# 07-DPLL-1.net
KiCad netlist of a schematic drawn in Altium Designer
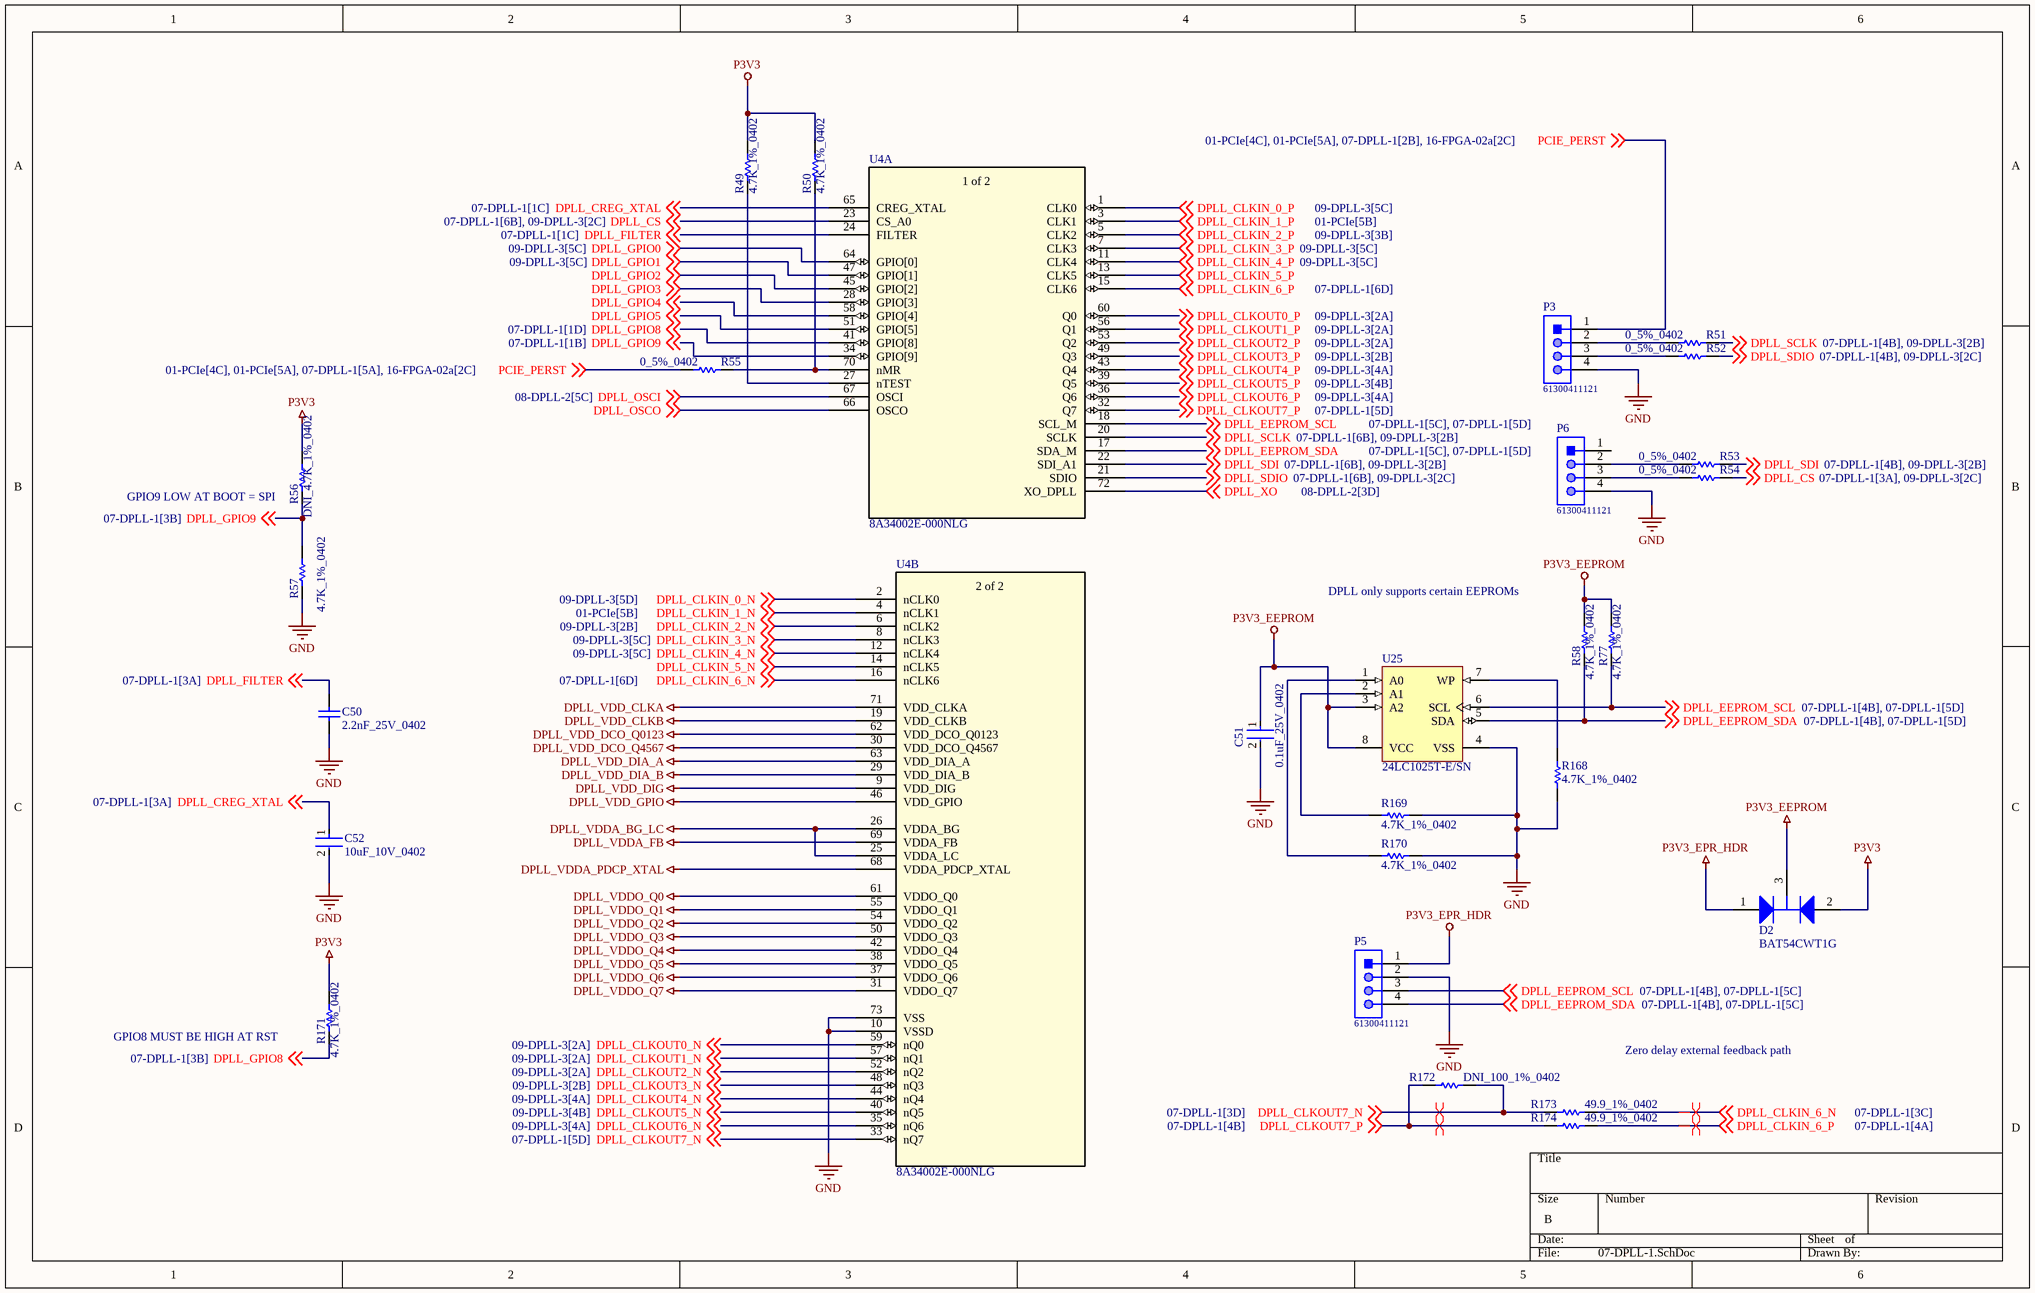
[diagram p0: 07-DPLL-1.SchDoc]

(export (version "E")
  (design (tool "Eeschema 10.0.6"))
  (components
    (comp (ref "C50")
      (value "2.2nF_25V_0402")
      (footprint "CAPC1005X56X25LL10T15")
      (fields
        (field (name "MANUFACTURER") "AVX Interconnect / Elco")
        (field (name "PART NUMBER") "04025C222JAT2A")
      )
      (libsource (lib "Altium Content Vault") (part "CAP"))
    )
    (comp (ref "C51")
      (value "0.1uF_25V_0402")
      (footprint "FP-0402-L_1_0_1-W_0_5_0_1-IPC_C")
      (description "General Purpose Ceramic Capacitor, 0402, 100nF, 10%, X7R, 15%, 25V")
      (fields (field (name "VOLTAGE") "25V") (field (name "TOLERANCE") "10%"))
      (libsource (lib "Altium Content Vault") (part "b4654b650e69147ec39a6b967a45e02"))
    )
    (comp (ref "C52")
      (value "10uF_10V_0402")
      (footprint "FP-CL05A106MP5NUNC-MFG")
      (description "CAP CER 10UF 10V X5R 0402")
      (fields
        (field (name "OCTOPART") "https://octopart.com/cl05a106mp5nunc-samsung-22457395")
        (field (name "TOLERANCE") "20%")
      )
      (libsource (lib "Altium Content Vault") (part "b4654b650e69147ec39a6b967a45e02"))
    )
    (comp (ref "D2")
      (value "BAT54CWT1G")
      (footprint "ONSC-SOT-323-3-419-04_V")
      (description "Dual Series Cathode Schottky Barrier Diodes, 3-Pin SOT-323, Pb-Free, Tape and Reel")
      (fields (field (name "MANUFACTURER") "On Semiconductor"))
      (libsource (lib "Altium Content Vault") (part "ONSC-D-A1A2K3-3"))
    )
    (comp (ref "P3")
      (value "61300411121")
      (footprint "61300411121")
      (description "THT Vertical Pin Header WR-PHD, Pitch 2.54 mm, Single Row, 4 pins")
      (fields (field (name "MANUFACTURER") "Wurth Elektronik") (field (name "PUBLISHER") "WurthElektronik"))
      (libsource (lib "Altium Content Vault") (part "WE-CN-1P-M-R4"))
    )
    (comp (ref "P5")
      (value "61300411121")
      (footprint "61300411121")
      (description "THT Vertical Pin Header WR-PHD, Pitch 2.54 mm, Single Row, 4 pins")
      (fields (field (name "MANUFACTURER") "Wurth Elektronik") (field (name "PUBLISHER") "WurthElektronik"))
      (libsource (lib "Altium Content Vault") (part "WE-CN-1P-M-R4"))
    )
    (comp (ref "P6")
      (value "61300411121")
      (footprint "61300411121")
      (description "THT Vertical Pin Header WR-PHD, Pitch 2.54 mm, Single Row, 4 pins")
      (fields (field (name "MANUFACTURER") "Wurth Elektronik") (field (name "PUBLISHER") "WurthElektronik"))
      (libsource (lib "Altium Content Vault") (part "WE-CN-1P-M-R4"))
    )
    (comp (ref "R49")
      (value "4.7K_1%_0402")
      (footprint "RESC1005X40X25NL10T10")
      (fields (field (name "MANUFACTURER") "Bourns") (field (name "PART NUMBER") "CR0402-FX-4701GLF"))
      (libsource (lib "Altium Content Vault") (part "RES"))
    )
    (comp (ref "R50")
      (value "4.7K_1%_0402")
      (footprint "RESC1005X40X25NL10T10")
      (fields (field (name "MANUFACTURER") "Bourns") (field (name "PART NUMBER") "CR0402-FX-4701GLF"))
      (libsource (lib "Altium Content Vault") (part "RES"))
    )
    (comp (ref "R51")
      (value "0_5%_0402")
      (footprint "RESC1005X40X25LL10T10")
      (fields (field (name "MANUFACTURER") "KOA Speer") (field (name "PART NUMBER") "RK73Z1ETTP"))
      (libsource (lib "Altium Content Vault") (part "RES"))
    )
    (comp (ref "R52")
      (value "0_5%_0402")
      (footprint "RESC1005X40X25LL10T10")
      (fields (field (name "MANUFACTURER") "KOA Speer") (field (name "PART NUMBER") "RK73Z1ETTP"))
      (libsource (lib "Altium Content Vault") (part "RES"))
    )
    (comp (ref "R53")
      (value "0_5%_0402")
      (footprint "RESC1005X40X25LL10T10")
      (fields (field (name "MANUFACTURER") "KOA Speer") (field (name "PART NUMBER") "RK73Z1ETTP"))
      (libsource (lib "Altium Content Vault") (part "RES"))
    )
    (comp (ref "R54")
      (value "0_5%_0402")
      (footprint "RESC1005X40X25LL10T10")
      (fields (field (name "MANUFACTURER") "KOA Speer") (field (name "PART NUMBER") "RK73Z1ETTP"))
      (libsource (lib "Altium Content Vault") (part "RES"))
    )
    (comp (ref "R55")
      (value "0_5%_0402")
      (footprint "RESC1005X40X25LL10T10")
      (fields (field (name "MANUFACTURER") "KOA Speer") (field (name "PART NUMBER") "RK73Z1ETTP"))
      (libsource (lib "Altium Content Vault") (part "RES"))
    )
    (comp (ref "R56")
      (value "DNI_4.7K_1%_0402")
      (footprint "RESC1005X40X25NL10T10")
      (fields (field (name "MANUFACTURER") "Bourns") (field (name "PART NUMBER") "CR0402-FX-4701GLF"))
      (libsource (lib "Altium Content Vault") (part "RES"))
    )
    (comp (ref "R57")
      (value "4.7K_1%_0402")
      (footprint "RESC1005X40X25NL10T10")
      (fields (field (name "MANUFACTURER") "Bourns") (field (name "PART NUMBER") "CR0402-FX-4701GLF"))
      (libsource (lib "Altium Content Vault") (part "RES"))
    )
    (comp (ref "R58")
      (value "4.7K_1%_0402")
      (footprint "RESC1005X40X25NL10T10")
      (fields (field (name "MANUFACTURER") "Bourns") (field (name "PART NUMBER") "CR0402-FX-4701GLF"))
      (libsource (lib "Altium Content Vault") (part "RES"))
    )
    (comp (ref "R77")
      (value "4.7K_1%_0402")
      (footprint "RESC1005X40X25NL10T10")
      (fields (field (name "MANUFACTURER") "Bourns") (field (name "PART NUMBER") "CR0402-FX-4701GLF"))
      (libsource (lib "Altium Content Vault") (part "RES"))
    )
    (comp (ref "R168")
      (value "4.7K_1%_0402")
      (footprint "RESC1005X40X25NL10T10")
      (fields (field (name "MANUFACTURER") "Bourns") (field (name "PART NUMBER") "CR0402-FX-4701GLF"))
      (libsource (lib "Altium Content Vault") (part "RES"))
    )
    (comp (ref "R169")
      (value "4.7K_1%_0402")
      (footprint "RESC1005X40X25NL10T10")
      (fields (field (name "MANUFACTURER") "Bourns") (field (name "PART NUMBER") "CR0402-FX-4701GLF"))
      (libsource (lib "Altium Content Vault") (part "RES"))
    )
    (comp (ref "R170")
      (value "4.7K_1%_0402")
      (footprint "RESC1005X40X25NL10T10")
      (fields (field (name "MANUFACTURER") "Bourns") (field (name "PART NUMBER") "CR0402-FX-4701GLF"))
      (libsource (lib "Altium Content Vault") (part "RES"))
    )
    (comp (ref "R171")
      (value "4.7K_1%_0402")
      (footprint "RESC1005X40X25NL10T10")
      (fields (field (name "MANUFACTURER") "Bourns") (field (name "PART NUMBER") "CR0402-FX-4701GLF"))
      (libsource (lib "Altium Content Vault") (part "RES"))
    )
    (comp (ref "R172")
      (value "DNI_100_1%_0402")
      (footprint "RESC1005X40X25LL05T05")
      (description "Chip Resistor, 100 Ohm, +/- 1%, 100 mW, -55 to 155 degC, 0402 (1005 Metric), RoHS, Tape and Reel")
      (fields (field (name "MANUFACTURER") "Basic Passives") (field (name "TOLERANCE") "1%"))
      (libsource (lib "Altium Content Vault") (part "RES-2"))
    )
    (comp (ref "R173")
      (value "49.9_1%_0402")
      (footprint "RESC1005X40X25NL10T10")
      (fields (field (name "PART NUMBER") "RK73H1ETTP49R9F") (field (name "MANUFACTURER") "KOA Speer"))
      (libsource (lib "Altium Content Vault") (part "RES"))
    )
    (comp (ref "R174")
      (value "49.9_1%_0402")
      (footprint "RESC1005X40X25NL10T10")
      (fields (field (name "PART NUMBER") "RK73H1ETTP49R9F") (field (name "MANUFACTURER") "KOA Speer"))
      (libsource (lib "Altium Content Vault") (part "RES"))
    )
    (comp (ref "U4")
      (value "8A34002E-000NLG")
      (footprint "QFN_2E-000NLG_REN")
      (description "No Description Available")
      (libsource (lib "8A34002E-000NLG") (part "8A34002E-000NLG"))
    )
    (comp (ref "U25")
      (value "24LC1025T-E/SN")
      (footprint "SOIC-SN8_M")
      (description "1 Mbit, 400kHz, 2.5V, 8-Pin SOIC 150mil, Extended Temperature, Tape and Reel")
      (libsource (lib "Altium Content Vault") (part "MEM-SEEPROM-34AA02-IL8"))
    )
  )
  (nets
    (net (code "1") (name "DPLL_CLKIN_0_N") (class "Default")
      (node (ref "U4") (pin "2") (pinfunction "nCLK0_2") (pintype "passive"))
    )
    (net (code "2") (name "DPLL_CLKIN_0_P") (class "Default")
      (node (ref "U4") (pin "1") (pinfunction "CLK0_1") (pintype "bidirectional"))
    )
    (net (code "3") (name "DPLL_CLKIN_1_N") (class "Default")
      (node (ref "U4") (pin "4") (pinfunction "nCLK1_4") (pintype "passive"))
    )
    (net (code "4") (name "DPLL_CLKIN_1_P") (class "Default")
      (node (ref "U4") (pin "3") (pinfunction "CLK1_3") (pintype "bidirectional"))
    )
    (net (code "5") (name "DPLL_CLKIN_2_N") (class "Default")
      (node (ref "U4") (pin "6") (pinfunction "nCLK2_6") (pintype "passive"))
    )
    (net (code "6") (name "DPLL_CLKIN_2_P") (class "Default")
      (node (ref "U4") (pin "5") (pinfunction "CLK2_5") (pintype "bidirectional"))
    )
    (net (code "7") (name "DPLL_CLKIN_3_N") (class "Default")
      (node (ref "U4") (pin "8") (pinfunction "nCLK3_8") (pintype "passive"))
    )
    (net (code "8") (name "DPLL_CLKIN_3_P") (class "Default")
      (node (ref "U4") (pin "7") (pinfunction "CLK3_7") (pintype "bidirectional"))
    )
    (net (code "9") (name "DPLL_CLKIN_4_N") (class "Default")
      (node (ref "U4") (pin "12") (pinfunction "nCLK4_12") (pintype "passive"))
    )
    (net (code "10") (name "DPLL_CLKIN_4_P") (class "Default")
      (node (ref "U4") (pin "11") (pinfunction "CLK4_11") (pintype "bidirectional"))
    )
    (net (code "11") (name "DPLL_CLKIN_5_N") (class "Default")
      (node (ref "U4") (pin "14") (pinfunction "nCLK5_14") (pintype "passive"))
    )
    (net (code "12") (name "DPLL_CLKIN_5_P") (class "Default")
      (node (ref "U4") (pin "13") (pinfunction "CLK5_13") (pintype "bidirectional"))
    )
    (net (code "13") (name "DPLL_CLKIN_6_N") (class "Default")
      (node (ref "R173") (pin "2") (pinfunction "2_2") (pintype "passive"))
      (node (ref "U4") (pin "16") (pinfunction "nCLK6_16") (pintype "passive"))
    )
    (net (code "14") (name "DPLL_CLKIN_6_P") (class "Default")
      (node (ref "R174") (pin "2") (pinfunction "2_2") (pintype "passive"))
      (node (ref "U4") (pin "15") (pinfunction "CLK6_15") (pintype "bidirectional"))
    )
    (net (code "15") (name "DPLL_CLKOUT0_N") (class "Default")
      (node (ref "U4") (pin "59") (pinfunction "nQ0_59") (pintype "bidirectional"))
    )
    (net (code "16") (name "DPLL_CLKOUT0_P") (class "Default")
      (node (ref "U4") (pin "60") (pinfunction "Q0_60") (pintype "bidirectional"))
    )
    (net (code "17") (name "DPLL_CLKOUT1_N") (class "Default")
      (node (ref "U4") (pin "57") (pinfunction "nQ1_57") (pintype "bidirectional"))
    )
    (net (code "18") (name "DPLL_CLKOUT1_P") (class "Default")
      (node (ref "U4") (pin "56") (pinfunction "Q1_56") (pintype "bidirectional"))
    )
    (net (code "19") (name "DPLL_CLKOUT2_N") (class "Default")
      (node (ref "U4") (pin "52") (pinfunction "nQ2_52") (pintype "bidirectional"))
    )
    (net (code "20") (name "DPLL_CLKOUT2_P") (class "Default")
      (node (ref "U4") (pin "53") (pinfunction "Q2_53") (pintype "bidirectional"))
    )
    (net (code "21") (name "DPLL_CLKOUT3_N") (class "Default")
      (node (ref "U4") (pin "48") (pinfunction "nQ3_48") (pintype "bidirectional"))
    )
    (net (code "22") (name "DPLL_CLKOUT3_P") (class "Default")
      (node (ref "U4") (pin "49") (pinfunction "Q3_49") (pintype "bidirectional"))
    )
    (net (code "23") (name "DPLL_CLKOUT4_N") (class "Default")
      (node (ref "U4") (pin "44") (pinfunction "nQ4_44") (pintype "bidirectional"))
    )
    (net (code "24") (name "DPLL_CLKOUT4_P") (class "Default")
      (node (ref "U4") (pin "43") (pinfunction "Q4_43") (pintype "bidirectional"))
    )
    (net (code "25") (name "DPLL_CLKOUT5_N") (class "Default")
      (node (ref "U4") (pin "40") (pinfunction "nQ5_40") (pintype "bidirectional"))
    )
    (net (code "26") (name "DPLL_CLKOUT5_P") (class "Default")
      (node (ref "U4") (pin "39") (pinfunction "Q5_39") (pintype "bidirectional"))
    )
    (net (code "27") (name "DPLL_CLKOUT6_N") (class "Default")
      (node (ref "U4") (pin "35") (pinfunction "nQ6_35") (pintype "bidirectional"))
    )
    (net (code "28") (name "DPLL_CLKOUT6_P") (class "Default")
      (node (ref "U4") (pin "36") (pinfunction "Q6_36") (pintype "bidirectional"))
    )
    (net (code "29") (name "DPLL_CLKOUT7_N") (class "Default")
      (node (ref "R172") (pin "2") (pinfunction "2_2") (pintype "passive"))
      (node (ref "R173") (pin "1") (pinfunction "1_1") (pintype "passive"))
      (node (ref "U4") (pin "33") (pinfunction "nQ7_33") (pintype "bidirectional"))
    )
    (net (code "30") (name "DPLL_CLKOUT7_P") (class "Default")
      (node (ref "R172") (pin "1") (pinfunction "1_1") (pintype "passive"))
      (node (ref "R174") (pin "1") (pinfunction "1_1") (pintype "passive"))
      (node (ref "U4") (pin "32") (pinfunction "Q7_32") (pintype "bidirectional"))
    )
    (net (code "31") (name "DPLL_CREG_XTAL") (class "Default")
      (node (ref "C52") (pin "1") (pinfunction "1_1") (pintype "passive"))
      (node (ref "U4") (pin "65") (pinfunction "CREG_XTAL_65") (pintype "passive"))
    )
    (net (code "32") (name "DPLL_CS") (class "Default")
      (node (ref "R54") (pin "2") (pinfunction "2_2") (pintype "passive"))
      (node (ref "U4") (pin "23") (pinfunction "CS_A0_23") (pintype "passive"))
    )
    (net (code "33") (name "DPLL_EEPROM_SCL") (class "Default")
      (node (ref "P5") (pin "3") (pinfunction "3_3") (pintype "passive"))
      (node (ref "R77") (pin "2") (pinfunction "2_2") (pintype "passive"))
      (node (ref "U25") (pin "6") (pinfunction "SCL_6") (pintype "input"))
      (node (ref "U4") (pin "18") (pinfunction "SCL_M_18") (pintype "passive"))
    )
    (net (code "34") (name "DPLL_EEPROM_SDA") (class "Default")
      (node (ref "P5") (pin "4") (pinfunction "4_4") (pintype "passive"))
      (node (ref "R58") (pin "2") (pinfunction "2_2") (pintype "passive"))
      (node (ref "U25") (pin "5") (pinfunction "SDA_5") (pintype "bidirectional"))
      (node (ref "U4") (pin "17") (pinfunction "SDA_M_17") (pintype "passive"))
    )
    (net (code "35") (name "DPLL_FILTER") (class "Default")
      (node (ref "C50") (pin "2") (pinfunction "2_2") (pintype "passive"))
      (node (ref "U4") (pin "24") (pinfunction "FILTER_24") (pintype "passive"))
    )
    (net (code "36") (name "DPLL_GPIO0") (class "Default")
      (node (ref "U4") (pin "64") (pinfunction "GPIO[0]_64") (pintype "bidirectional"))
    )
    (net (code "37") (name "DPLL_GPIO1") (class "Default")
      (node (ref "U4") (pin "47") (pinfunction "GPIO[1]_47") (pintype "bidirectional"))
    )
    (net (code "38") (name "DPLL_GPIO2") (class "Default")
      (node (ref "U4") (pin "45") (pinfunction "GPIO[2]_45") (pintype "bidirectional"))
    )
    (net (code "39") (name "DPLL_GPIO3") (class "Default")
      (node (ref "U4") (pin "28") (pinfunction "GPIO[3]_28") (pintype "bidirectional"))
    )
    (net (code "40") (name "DPLL_GPIO4") (class "Default")
      (node (ref "U4") (pin "58") (pinfunction "GPIO[4]_58") (pintype "bidirectional"))
    )
    (net (code "41") (name "DPLL_GPIO5") (class "Default")
      (node (ref "U4") (pin "51") (pinfunction "GPIO[5]_51") (pintype "bidirectional"))
    )
    (net (code "42") (name "DPLL_GPIO8") (class "Default")
      (node (ref "R171") (pin "2") (pinfunction "2_2") (pintype "passive"))
      (node (ref "U4") (pin "41") (pinfunction "GPIO[8]_41") (pintype "bidirectional"))
    )
    (net (code "43") (name "DPLL_GPIO9") (class "Default")
      (node (ref "R56") (pin "2") (pinfunction "2_2") (pintype "passive"))
      (node (ref "R57") (pin "2") (pinfunction "2_2") (pintype "passive"))
      (node (ref "U4") (pin "34") (pinfunction "GPIO[9]_34") (pintype "bidirectional"))
    )
    (net (code "44") (name "DPLL_OSCI") (class "Default")
      (node (ref "U4") (pin "67") (pinfunction "OSCI_67") (pintype "passive"))
    )
    (net (code "45") (name "DPLL_OSCO") (class "Default")
      (node (ref "U4") (pin "66") (pinfunction "OSCO_66") (pintype "passive"))
    )
    (net (code "46") (name "DPLL_SCLK") (class "Default")
      (node (ref "R51") (pin "2") (pinfunction "2_2") (pintype "passive"))
      (node (ref "U4") (pin "20") (pinfunction "SCLK_20") (pintype "passive"))
    )
    (net (code "47") (name "DPLL_SDI") (class "Default")
      (node (ref "R53") (pin "2") (pinfunction "2_2") (pintype "passive"))
      (node (ref "U4") (pin "22") (pinfunction "SDI_A1_22") (pintype "passive"))
    )
    (net (code "48") (name "DPLL_SDIO") (class "Default")
      (node (ref "R52") (pin "2") (pinfunction "2_2") (pintype "passive"))
      (node (ref "U4") (pin "21") (pinfunction "SDIO_21") (pintype "passive"))
    )
    (net (code "49") (name "DPLL_VDDA_BG_LC") (class "Default")
      (node (ref "U4") (pin "25") (pinfunction "VDDA_LC_25") (pintype "power_in"))
      (node (ref "U4") (pin "26") (pinfunction "VDDA_BG_26") (pintype "power_in"))
    )
    (net (code "50") (name "DPLL_VDDA_FB") (class "Default")
      (node (ref "U4") (pin "69") (pinfunction "VDDA_FB_69") (pintype "power_in"))
    )
    (net (code "51") (name "DPLL_VDDA_PDCP_XTAL") (class "Default")
      (node (ref "U4") (pin "68") (pinfunction "VDDA_PDCP_XTAL_68") (pintype "power_in"))
    )
    (net (code "52") (name "DPLL_VDDO_Q0") (class "Default")
      (node (ref "U4") (pin "61") (pinfunction "VDDO_Q0_61") (pintype "power_in"))
    )
    (net (code "53") (name "DPLL_VDDO_Q1") (class "Default")
      (node (ref "U4") (pin "55") (pinfunction "VDDO_Q1_55") (pintype "power_in"))
    )
    (net (code "54") (name "DPLL_VDDO_Q2") (class "Default")
      (node (ref "U4") (pin "54") (pinfunction "VDDO_Q2_54") (pintype "power_in"))
    )
    (net (code "55") (name "DPLL_VDDO_Q3") (class "Default")
      (node (ref "U4") (pin "50") (pinfunction "VDDO_Q3_50") (pintype "power_in"))
    )
    (net (code "56") (name "DPLL_VDDO_Q4") (class "Default")
      (node (ref "U4") (pin "42") (pinfunction "VDDO_Q4_42") (pintype "power_in"))
    )
    (net (code "57") (name "DPLL_VDDO_Q5") (class "Default")
      (node (ref "U4") (pin "38") (pinfunction "VDDO_Q5_38") (pintype "power_in"))
    )
    (net (code "58") (name "DPLL_VDDO_Q6") (class "Default")
      (node (ref "U4") (pin "37") (pinfunction "VDDO_Q6_37") (pintype "power_in"))
    )
    (net (code "59") (name "DPLL_VDDO_Q7") (class "Default")
      (node (ref "U4") (pin "31") (pinfunction "VDDO_Q7_31") (pintype "power_in"))
    )
    (net (code "60") (name "DPLL_VDD_CLKA") (class "Default")
      (node (ref "U4") (pin "71") (pinfunction "VDD_CLKA_71") (pintype "power_in"))
    )
    (net (code "61") (name "DPLL_VDD_CLKB") (class "Default")
      (node (ref "U4") (pin "19") (pinfunction "VDD_CLKB_19") (pintype "power_in"))
    )
    (net (code "62") (name "DPLL_VDD_DCO_Q0123") (class "Default")
      (node (ref "U4") (pin "62") (pinfunction "VDD_DCO_Q0123_62") (pintype "power_in"))
    )
    (net (code "63") (name "DPLL_VDD_DCO_Q4567") (class "Default")
      (node (ref "U4") (pin "30") (pinfunction "VDD_DCO_Q4567_30") (pintype "power_in"))
    )
    (net (code "64") (name "DPLL_VDD_DIA_A") (class "Default")
      (node (ref "U4") (pin "63") (pinfunction "VDD_DIA_A_63") (pintype "power_in"))
    )
    (net (code "65") (name "DPLL_VDD_DIA_B") (class "Default")
      (node (ref "U4") (pin "29") (pinfunction "VDD_DIA_B_29") (pintype "power_in"))
    )
    (net (code "66") (name "DPLL_VDD_DIG") (class "Default")
      (node (ref "U4") (pin "9") (pinfunction "VDD_DIG_9") (pintype "power_in"))
    )
    (net (code "67") (name "DPLL_VDD_GPIO") (class "Default")
      (node (ref "U4") (pin "46") (pinfunction "VDD_GPIO_46") (pintype "power_in"))
    )
    (net (code "68") (name "DPLL_XO") (class "Default")
      (node (ref "U4") (pin "72") (pinfunction "XO_DPLL_72") (pintype "passive"))
    )
    (net (code "69") (name "GND") (class "Default")
      (node (ref "C50") (pin "1") (pinfunction "1_1") (pintype "passive"))
      (node (ref "C51") (pin "2") (pinfunction "2_2") (pintype "passive"))
      (node (ref "C52") (pin "2") (pinfunction "2_2") (pintype "passive"))
      (node (ref "P3") (pin "4") (pinfunction "4_4") (pintype "passive"))
      (node (ref "P5") (pin "2") (pinfunction "2_2") (pintype "passive"))
      (node (ref "P6") (pin "4") (pinfunction "4_4") (pintype "passive"))
      (node (ref "R168") (pin "2") (pinfunction "2_2") (pintype "passive"))
      (node (ref "R169") (pin "1") (pinfunction "1_1") (pintype "passive"))
      (node (ref "R170") (pin "2") (pinfunction "2_2") (pintype "passive"))
      (node (ref "R57") (pin "1") (pinfunction "1_1") (pintype "passive"))
      (node (ref "U25") (pin "4") (pinfunction "VSS_4") (pintype "power_in"))
      (node (ref "U4") (pin "10") (pinfunction "VSSD_10") (pintype "power_in"))
      (node (ref "U4") (pin "73") (pinfunction "VSS_73") (pintype "power_in"))
    )
    (net (code "70") (name "Net-(P3-Pad2)") (class "Default")
      (node (ref "P3") (pin "2") (pinfunction "2_2") (pintype "passive"))
      (node (ref "R51") (pin "1") (pinfunction "1_1") (pintype "passive"))
    )
    (net (code "71") (name "Net-(P3-Pad3)") (class "Default")
      (node (ref "P3") (pin "3") (pinfunction "3_3") (pintype "passive"))
      (node (ref "R52") (pin "1") (pinfunction "1_1") (pintype "passive"))
    )
    (net (code "72") (name "Net-(P6-Pad2)") (class "Default")
      (node (ref "P6") (pin "2") (pinfunction "2_2") (pintype "passive"))
      (node (ref "R53") (pin "1") (pinfunction "1_1") (pintype "passive"))
    )
    (net (code "73") (name "Net-(P6-Pad3)") (class "Default")
      (node (ref "P6") (pin "3") (pinfunction "3_3") (pintype "passive"))
      (node (ref "R54") (pin "1") (pinfunction "1_1") (pintype "passive"))
    )
    (net (code "74") (name "Net-(U4A-nMR)") (class "Default")
      (node (ref "R50") (pin "1") (pinfunction "1_1") (pintype "passive"))
      (node (ref "R55") (pin "2") (pinfunction "2_2") (pintype "passive"))
      (node (ref "U4") (pin "70") (pinfunction "nMR_70") (pintype "passive"))
    )
    (net (code "75") (name "Net-(U4A-nTEST)") (class "Default")
      (node (ref "R49") (pin "1") (pinfunction "1_1") (pintype "passive"))
      (node (ref "U4") (pin "27") (pinfunction "nTEST_27") (pintype "passive"))
    )
    (net (code "76") (name "Net-(U25-A0)") (class "Default")
      (node (ref "R170") (pin "1") (pinfunction "1_1") (pintype "passive"))
      (node (ref "U25") (pin "1") (pinfunction "A0_1") (pintype "input"))
    )
    (net (code "77") (name "Net-(U25-A1)") (class "Default")
      (node (ref "R169") (pin "2") (pinfunction "2_2") (pintype "passive"))
      (node (ref "U25") (pin "2") (pinfunction "A1_2") (pintype "input"))
    )
    (net (code "78") (name "Net-(U25-WP)") (class "Default")
      (node (ref "R168") (pin "1") (pinfunction "1_1") (pintype "passive"))
      (node (ref "U25") (pin "7") (pinfunction "WP_7") (pintype "input"))
    )
    (net (code "79") (name "P3V3") (class "Default")
      (node (ref "D2") (pin "2") (pinfunction "A2_2") (pintype "passive"))
      (node (ref "R171") (pin "1") (pinfunction "1_1") (pintype "passive"))
      (node (ref "R49") (pin "2") (pinfunction "2_2") (pintype "passive"))
      (node (ref "R50") (pin "2") (pinfunction "2_2") (pintype "passive"))
      (node (ref "R56") (pin "1") (pinfunction "1_1") (pintype "passive"))
    )
    (net (code "80") (name "P3V3_EEPROM") (class "Default")
      (node (ref "C51") (pin "1") (pinfunction "1_1") (pintype "passive"))
      (node (ref "D2") (pin "3") (pinfunction "K_3") (pintype "passive"))
      (node (ref "R58") (pin "1") (pinfunction "1_1") (pintype "passive"))
      (node (ref "R77") (pin "1") (pinfunction "1_1") (pintype "passive"))
      (node (ref "U25") (pin "3") (pinfunction "A2_3") (pintype "input"))
      (node (ref "U25") (pin "8") (pinfunction "VCC_8") (pintype "power_in"))
    )
    (net (code "81") (name "P3V3_EPR_HDR") (class "Default")
      (node (ref "D2") (pin "1") (pinfunction "A1_1") (pintype "passive"))
      (node (ref "P5") (pin "1") (pinfunction "1_1") (pintype "passive"))
    )
    (net (code "82") (name "PCIE_PERST") (class "Default")
      (node (ref "P3") (pin "1") (pinfunction "1_1") (pintype "passive"))
      (node (ref "R55") (pin "1") (pinfunction "1_1") (pintype "passive"))
    )
    (net (code "83") (name "unconnected-(P6-Pad1)") (class "Default")
      (node (ref "P6") (pin "1") (pinfunction "1_1") (pintype "passive"))
    )
  )
)
